# Sheet2.net
KiCad netlist of a schematic drawn in Altium Designer
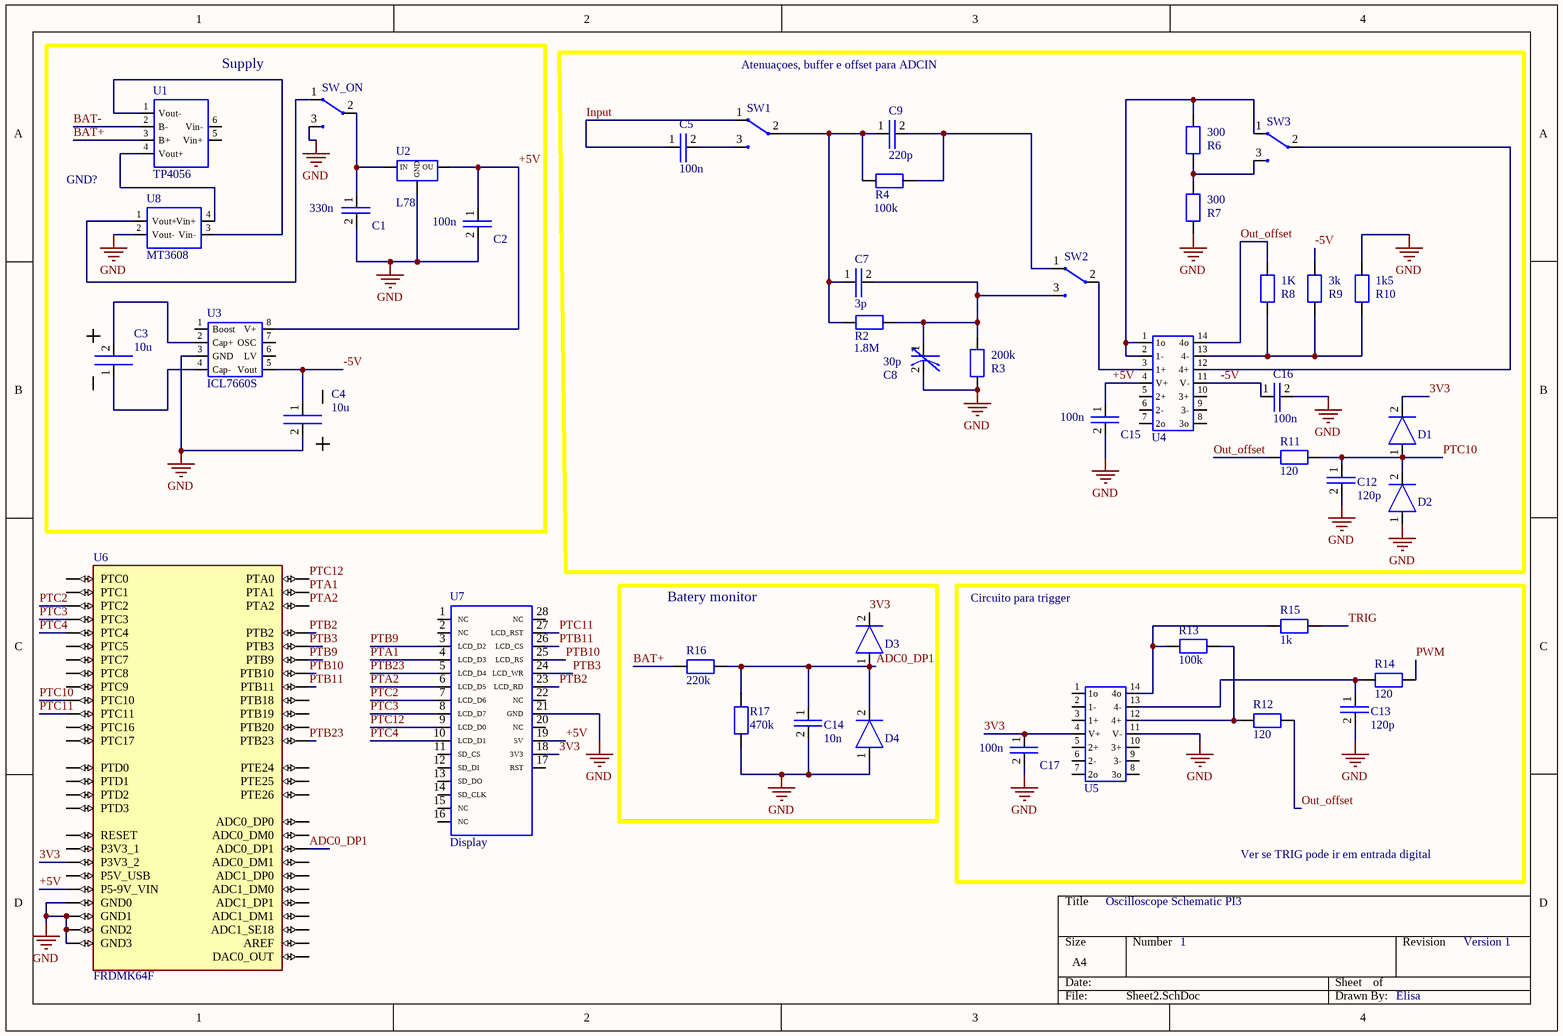
[diagram p0: Sheet2.SchDoc]

(export (version "E")
  (design (tool "Eeschema 10.0.6"))
  (components
    (comp (ref "C1")
      (value "330n")
      (footprint "CAP_CER_THT")
      (libsource (lib "Schlib2") (part "Capacitor_THT"))
    )
    (comp (ref "C2")
      (value "100n")
      (footprint "CAP_CER_THT")
      (libsource (lib "Schlib2") (part "Capacitor_THT"))
    )
    (comp (ref "C3")
      (value "10u")
      (footprint "CAP_THT")
      (description "CAP ALUM 47UF 20% 25V RADIAL TH")
      (libsource (lib "Schlib2") (part "EEU-FC1E470"))
    )
    (comp (ref "C4")
      (value "10u")
      (footprint "CAP_THT")
      (description "CAP ALUM 47UF 20% 25V RADIAL TH")
      (libsource (lib "Schlib2") (part "EEU-FC1E470"))
    )
    (comp (ref "C5")
      (value "100n")
      (footprint "CAP_CER_THT")
      (libsource (lib "Schlib2") (part "Capacitor_THT"))
    )
    (comp (ref "C7")
      (value "3p")
      (footprint "CAP_CER_THT")
      (libsource (lib "Schlib2") (part "Capacitor_THT"))
    )
    (comp (ref "C8")
      (value "30p")
      (footprint "CAP_TRIMM_THT")
      (libsource (lib "Schlib2") (part "CAP_TRIMM_THT"))
    )
    (comp (ref "C9")
      (value "220p")
      (footprint "CAP_CER_THT")
      (libsource (lib "Schlib2") (part "Capacitor_THT"))
    )
    (comp (ref "C12")
      (value "120p")
      (footprint "CAP_CER_THT")
      (libsource (lib "Schlib2") (part "Capacitor_THT"))
    )
    (comp (ref "C13")
      (value "120p")
      (footprint "CAP_CER_THT")
      (libsource (lib "Schlib2") (part "Capacitor_THT"))
    )
    (comp (ref "C14")
      (value "10n")
      (footprint "CAP_CER_THT")
      (libsource (lib "Schlib2") (part "Capacitor_THT"))
    )
    (comp (ref "C15")
      (value "100n")
      (footprint "CAP_CER_THT")
      (libsource (lib "Schlib2") (part "Capacitor_THT"))
    )
    (comp (ref "C16")
      (value "100n")
      (footprint "CAP_CER_THT")
      (libsource (lib "Schlib2") (part "Capacitor_THT"))
    )
    (comp (ref "C17")
      (value "100n")
      (footprint "CAP_CER_THT")
      (libsource (lib "Schlib2") (part "Capacitor_THT"))
    )
    (comp (ref "D1")
      (value "diode_1N4148")
      (footprint "SOD323F_DIODE")
      (libsource (lib "Schlib2") (part "diode_1N4148"))
    )
    (comp (ref "D2")
      (value "diode_1N4148")
      (footprint "SOD323F_DIODE")
      (libsource (lib "Schlib2") (part "diode_1N4148"))
    )
    (comp (ref "D3")
      (value "diode_1N4148")
      (footprint "SOD323F_DIODE")
      (libsource (lib "Schlib2") (part "diode_1N4148"))
    )
    (comp (ref "D4")
      (value "diode_1N4148")
      (footprint "SOD323F_DIODE")
      (libsource (lib "Schlib2") (part "diode_1N4148"))
    )
    (comp (ref "R2") (value "1.8M") (footprint "RES_THT") (libsource (lib "Schlib2") (part "RES_THT")))
    (comp (ref "R3") (value "200k") (footprint "RES_THT") (libsource (lib "Schlib2") (part "RES_THT")))
    (comp (ref "R4") (value "100k") (footprint "RES_THT") (libsource (lib "Schlib2") (part "RES_THT")))
    (comp (ref "R6") (value "300") (footprint "RES_THT") (libsource (lib "Schlib2") (part "RES_THT")))
    (comp (ref "R7") (value "300") (footprint "RES_THT") (libsource (lib "Schlib2") (part "RES_THT")))
    (comp (ref "R8") (value "1K") (footprint "RES_THT") (libsource (lib "Schlib2") (part "RES_THT")))
    (comp (ref "R9") (value "3k") (footprint "RES_THT") (libsource (lib "Schlib2") (part "RES_THT")))
    (comp (ref "R10") (value "1k5") (footprint "RES_THT") (libsource (lib "Schlib2") (part "RES_THT")))
    (comp (ref "R11") (value "120") (footprint "RES_THT") (libsource (lib "Schlib2") (part "RES_THT")))
    (comp (ref "R12") (value "120") (footprint "RES_THT") (libsource (lib "Schlib2") (part "RES_THT")))
    (comp (ref "R13") (value "100k") (footprint "RES_THT") (libsource (lib "Schlib2") (part "RES_THT")))
    (comp (ref "R14") (value "120") (footprint "RES_THT") (libsource (lib "Schlib2") (part "RES_THT")))
    (comp (ref "R15") (value "1k") (footprint "RES_THT") (libsource (lib "Schlib2") (part "RES_THT")))
    (comp (ref "R16") (value "220k") (footprint "RES_THT") (libsource (lib "Schlib2") (part "RES_THT")))
    (comp (ref "R17") (value "470k") (footprint "RES_THT") (libsource (lib "Schlib2") (part "RES_THT")))
    (comp (ref "SW1") (value "SW") (footprint "SW") (libsource (lib "Schlib2") (part "SW")))
    (comp (ref "SW2") (value "SW") (footprint "SW") (libsource (lib "Schlib2") (part "SW")))
    (comp (ref "SW3") (value "SW") (footprint "SW") (libsource (lib "Schlib2") (part "SW")))
    (comp (ref "SW_ON") (value "SW") (footprint "SW") (libsource (lib "Schlib2") (part "SW")))
    (comp (ref "U1") (value "TP4056") (footprint "TP0456") (libsource (lib "Schlib2") (part "TP4056")))
    (comp (ref "U2")
      (value "L78")
      (footprint "TO-220-3")
      (description "IC REG LINEAR 5V 1.5A")
      (libsource (lib "Schlib2") (part "L7805CDT-TR"))
    )
    (comp (ref "U3") (value "ICL7660S") (footprint "8 -PDIP") (libsource (lib "Schlib2") (part "ICL7660S")))
    (comp (ref "U4") (value "TL084CN") (footprint "14-PDIP") (libsource (lib "Schlib2") (part "TL084CN")))
    (comp (ref "U5") (value "TL084CN") (footprint "14-PDIP") (libsource (lib "Schlib2") (part "TL084CN")))
    (comp (ref "U6") (value "FRDMK64F") (footprint "FRDMK64F") (libsource (lib "Schlib2") (part "FRDMK64F")))
    (comp (ref "U7") (value "Display") (footprint "Display") (libsource (lib "Schlib2") (part "Display")))
    (comp (ref "U8") (value "MT3608") (footprint "MT3608") (libsource (lib "Schlib2") (part "MT3608")))
  )
  (nets
    (net (code "1") (name "/+5V") (class "Default")
      (node (ref "C15") (pin "1") (pinfunction "1_1") (pintype "passive"))
      (node (ref "C2") (pin "1") (pinfunction "1_1") (pintype "passive"))
      (node (ref "U2") (pin "3") (pinfunction "OU_3") (pintype "passive"))
      (node (ref "U3") (pin "8") (pinfunction "V+_8") (pintype "passive"))
      (node (ref "U4") (pin "4") (pinfunction "V+_4") (pintype "passive"))
      (node (ref "U6") (pin "J3-16") (pinfunction "P5-9V_VIN_J3-16") (pintype "bidirectional"))
      (node (ref "U7") (pin "19") (pinfunction "5V_19") (pintype "passive"))
    )
    (net (code "2") (name "/-5V") (class "Default")
      (node (ref "C16") (pin "1") (pinfunction "1_1") (pintype "passive"))
      (node (ref "C4") (pin "1") (pinfunction "1_1") (pintype "passive"))
      (node (ref "R9") (pin "2") (pinfunction "2_2") (pintype "passive"))
      (node (ref "U3") (pin "5") (pinfunction "Vout_5") (pintype "passive"))
      (node (ref "U4") (pin "11") (pinfunction "V-_11") (pintype "passive"))
    )
    (net (code "3") (name "/3V3") (class "Default")
      (node (ref "C17") (pin "1") (pinfunction "1_1") (pintype "passive"))
      (node (ref "D1") (pin "2") (pintype "passive"))
      (node (ref "D3") (pin "2") (pintype "passive"))
      (node (ref "U5") (pin "4") (pinfunction "V+_4") (pintype "passive"))
      (node (ref "U6") (pin "J3-8") (pinfunction "P3V3_2_J3-8") (pintype "bidirectional"))
      (node (ref "U7") (pin "18") (pinfunction "3V3_18") (pintype "passive"))
    )
    (net (code "4") (name "/ADC0_DP1") (class "Default")
      (node (ref "C14") (pin "1") (pinfunction "1_1") (pintype "passive"))
      (node (ref "D3") (pin "1") (pintype "passive"))
      (node (ref "D4") (pin "2") (pintype "passive"))
      (node (ref "R16") (pin "1") (pinfunction "1_1") (pintype "passive"))
      (node (ref "R17") (pin "1") (pinfunction "1_1") (pintype "passive"))
      (node (ref "U6") (pin "J4-1") (pinfunction "ADC0_DP1_J4-1") (pintype "bidirectional"))
    )
    (net (code "5") (name "/BAT+") (class "Default")
      (node (ref "R16") (pin "2") (pinfunction "2_2") (pintype "passive"))
      (node (ref "U1") (pin "3") (pinfunction "B+_3") (pintype "passive"))
    )
    (net (code "6") (name "/BAT-") (class "Default")
      (node (ref "U1") (pin "2") (pinfunction "B-_2") (pintype "passive"))
    )
    (net (code "7") (name "/Input") (class "Default")
      (node (ref "C5") (pin "1") (pinfunction "1_1") (pintype "passive"))
      (node (ref "SW1") (pin "1") (pinfunction "1_1") (pintype "passive"))
    )
    (net (code "8") (name "/Out_offset") (class "Default")
      (node (ref "R11") (pin "2") (pinfunction "2_2") (pintype "passive"))
      (node (ref "R12") (pin "1") (pinfunction "1_1") (pintype "passive"))
      (node (ref "R8") (pin "2") (pinfunction "2_2") (pintype "passive"))
      (node (ref "U4") (pin "14") (pinfunction "4o_14") (pintype "passive"))
    )
    (net (code "9") (name "/PTA1") (class "Default")
      (node (ref "U6") (pin "J1-8") (pinfunction "PTA1_J1-8") (pintype "bidirectional"))
      (node (ref "U7") (pin "4") (pinfunction "LCD_D3_4") (pintype "passive"))
    )
    (net (code "10") (name "/PTA2") (class "Default")
      (node (ref "U6") (pin "J1-12") (pinfunction "PTA2_J1-12") (pintype "bidirectional"))
      (node (ref "U7") (pin "6") (pinfunction "LCD_D5_6") (pintype "passive"))
    )
    (net (code "11") (name "/PTB2") (class "Default")
      (node (ref "U6") (pin "J4-2") (pinfunction "PTB2_J4-2") (pintype "bidirectional"))
      (node (ref "U7") (pin "23") (pinfunction "LCD_RD_23") (pintype "passive"))
    )
    (net (code "12") (name "/PTB3") (class "Default")
      (node (ref "U6") (pin "J4-4") (pinfunction "PTB3_J4-4") (pintype "bidirectional"))
      (node (ref "U7") (pin "24") (pinfunction "LCD_WR_24") (pintype "passive"))
    )
    (net (code "13") (name "/PTB9") (class "Default")
      (node (ref "U6") (pin "J1-6") (pinfunction "PTB9_J1-6") (pintype "bidirectional"))
      (node (ref "U7") (pin "3") (pinfunction "LCD_D2_3") (pintype "passive"))
    )
    (net (code "14") (name "/PTB10") (class "Default")
      (node (ref "U6") (pin "J4-6") (pinfunction "PTB10_J4-6") (pintype "bidirectional"))
      (node (ref "U7") (pin "25") (pinfunction "LCD_RS_25") (pintype "passive"))
    )
    (net (code "15") (name "/PTB11") (class "Default")
      (node (ref "U6") (pin "J4-8") (pinfunction "PTB11_J4-8") (pintype "bidirectional"))
      (node (ref "U7") (pin "26") (pinfunction "LCD_CS_26") (pintype "passive"))
    )
    (net (code "16") (name "/PTB23") (class "Default")
      (node (ref "U6") (pin "J1-10") (pinfunction "PTB23_J1-10") (pintype "bidirectional"))
      (node (ref "U7") (pin "5") (pinfunction "LCD_D4_5") (pintype "passive"))
    )
    (net (code "17") (name "/PTC2") (class "Default")
      (node (ref "U6") (pin "J1-14") (pinfunction "PTC2_J1-14") (pintype "bidirectional"))
      (node (ref "U7") (pin "7") (pinfunction "LCD_D6_7") (pintype "passive"))
    )
    (net (code "18") (name "/PTC3") (class "Default")
      (node (ref "U6") (pin "J1-16") (pinfunction "PTC3_J1-16") (pintype "bidirectional"))
      (node (ref "U7") (pin "8") (pinfunction "LCD_D7_8") (pintype "passive"))
    )
    (net (code "19") (name "/PTC4") (class "Default")
      (node (ref "U6") (pin "J2-4") (pinfunction "PTC4_J2-4") (pintype "bidirectional"))
      (node (ref "U7") (pin "10") (pinfunction "LCD_D1_10") (pintype "passive"))
    )
    (net (code "20") (name "/PTC10") (class "Default")
      (node (ref "C12") (pin "1") (pinfunction "1_1") (pintype "passive"))
      (node (ref "D1") (pin "1") (pintype "passive"))
      (node (ref "D2") (pin "2") (pintype "passive"))
      (node (ref "R11") (pin "1") (pinfunction "1_1") (pintype "passive"))
      (node (ref "U6") (pin "J4-12") (pinfunction "PTC10_J4-12") (pintype "bidirectional"))
    )
    (net (code "21") (name "/PTC11") (class "Default")
      (node (ref "U6") (pin "J4-10") (pinfunction "PTC11_J4-10") (pintype "bidirectional"))
      (node (ref "U7") (pin "27") (pinfunction "LCD_RST_27") (pintype "passive"))
    )
    (net (code "22") (name "/PTC12") (class "Default")
      (node (ref "U6") (pin "J2-2") (pinfunction "PTA0_J2-2") (pintype "bidirectional"))
      (node (ref "U7") (pin "9") (pinfunction "LCD_D0_9") (pintype "passive"))
    )
    (net (code "23") (name "/PWM") (class "Default")
      (node (ref "R14") (pin "1") (pinfunction "1_1") (pintype "passive"))
    )
    (net (code "24") (name "/TRIG") (class "Default")
      (node (ref "R15") (pin "2") (pinfunction "2_2") (pintype "passive"))
    )
    (net (code "25") (name "GND") (class "Default")
      (node (ref "C1") (pin "2") (pinfunction "0_2") (pintype "passive"))
      (node (ref "C12") (pin "2") (pinfunction "0_2") (pintype "passive"))
      (node (ref "C13") (pin "2") (pinfunction "0_2") (pintype "passive"))
      (node (ref "C14") (pin "2") (pinfunction "0_2") (pintype "passive"))
      (node (ref "C15") (pin "2") (pinfunction "0_2") (pintype "passive"))
      (node (ref "C16") (pin "2") (pinfunction "0_2") (pintype "passive"))
      (node (ref "C17") (pin "2") (pinfunction "0_2") (pintype "passive"))
      (node (ref "C2") (pin "2") (pinfunction "0_2") (pintype "passive"))
      (node (ref "C4") (pin "2") (pinfunction "0_2") (pintype "passive"))
      (node (ref "C8") (pin "2") (pinfunction "0_2") (pintype "passive"))
      (node (ref "D2") (pin "1") (pintype "passive"))
      (node (ref "D4") (pin "1") (pintype "passive"))
      (node (ref "R10") (pin "2") (pinfunction "2_2") (pintype "passive"))
      (node (ref "R17") (pin "2") (pinfunction "2_2") (pintype "passive"))
      (node (ref "R3") (pin "1") (pinfunction "1_1") (pintype "passive"))
      (node (ref "R7") (pin "1") (pinfunction "1_1") (pintype "passive"))
      (node (ref "SW_ON") (pin "3") (pinfunction "3_3") (pintype "passive"))
      (node (ref "U2") (pin "2") (pinfunction "GND_2") (pintype "passive"))
      (node (ref "U3") (pin "3") (pinfunction "GND_3") (pintype "passive"))
      (node (ref "U5") (pin "11") (pinfunction "V-_11") (pintype "passive"))
      (node (ref "U6") (pin "J2-14") (pinfunction "GND1_J2-14") (pintype "bidirectional"))
      (node (ref "U6") (pin "J2-3") (pinfunction "GND0_J2-3") (pintype "bidirectional"))
      (node (ref "U6") (pin "J3-12") (pinfunction "GND2_J3-12") (pintype "bidirectional"))
      (node (ref "U6") (pin "J3-14") (pinfunction "GND3_J3-14") (pintype "bidirectional"))
      (node (ref "U7") (pin "21") (pinfunction "GND_21") (pintype "passive"))
      (node (ref "U8") (pin "2") (pinfunction "Vout-_2") (pintype "passive"))
    )
    (net (code "26") (name "Net-(C3-0)") (class "Default")
      (node (ref "C3") (pin "2") (pinfunction "0_2") (pintype "passive"))
      (node (ref "U3") (pin "2") (pinfunction "Cap+_2") (pintype "passive"))
    )
    (net (code "27") (name "Net-(C5-0)") (class "Default")
      (node (ref "C5") (pin "2") (pinfunction "0_2") (pintype "passive"))
      (node (ref "SW1") (pin "3") (pinfunction "3_3") (pintype "passive"))
    )
    (net (code "28") (name "Net-(C7-0)") (class "Default")
      (node (ref "C7") (pin "2") (pinfunction "0_2") (pintype "passive"))
      (node (ref "C8") (pin "1") (pinfunction "1_1") (pintype "passive"))
      (node (ref "R2") (pin "2") (pinfunction "2_2") (pintype "passive"))
      (node (ref "R3") (pin "2") (pinfunction "2_2") (pintype "passive"))
      (node (ref "SW2") (pin "3") (pinfunction "3_3") (pintype "passive"))
    )
    (net (code "29") (name "Net-(C7-Pad1)") (class "Default")
      (node (ref "C7") (pin "1") (pinfunction "1_1") (pintype "passive"))
      (node (ref "C9") (pin "1") (pinfunction "1_1") (pintype "passive"))
      (node (ref "R2") (pin "1") (pinfunction "1_1") (pintype "passive"))
      (node (ref "R4") (pin "1") (pinfunction "1_1") (pintype "passive"))
      (node (ref "SW1") (pin "2") (pinfunction "2_2") (pintype "passive"))
    )
    (net (code "30") (name "Net-(C9-0)") (class "Default")
      (node (ref "C9") (pin "2") (pinfunction "0_2") (pintype "passive"))
      (node (ref "R4") (pin "2") (pinfunction "2_2") (pintype "passive"))
      (node (ref "SW2") (pin "1") (pinfunction "1_1") (pintype "passive"))
    )
    (net (code "31") (name "Net-(R6-Pad1)") (class "Default")
      (node (ref "R6") (pin "1") (pinfunction "1_1") (pintype "passive"))
      (node (ref "R7") (pin "2") (pinfunction "2_2") (pintype "passive"))
      (node (ref "SW3") (pin "3") (pinfunction "3_3") (pintype "passive"))
    )
    (net (code "32") (name "Net-(U1-Vout+)") (class "Default")
      (node (ref "U1") (pin "4") (pinfunction "Vout+_4") (pintype "passive"))
      (node (ref "U8") (pin "4") (pinfunction "Vin+_4") (pintype "passive"))
    )
    (net (code "33") (name "Net-(U1-Vout-)") (class "Default")
      (node (ref "U1") (pin "1") (pinfunction "Vout-_1") (pintype "passive"))
      (node (ref "U8") (pin "3") (pinfunction "Vin-_3") (pintype "passive"))
    )
    (net (code "34") (name "Net-(U2-IN)") (class "Default")
      (node (ref "C1") (pin "1") (pinfunction "1_1") (pintype "passive"))
      (node (ref "SW_ON") (pin "2") (pinfunction "2_2") (pintype "passive"))
      (node (ref "U2") (pin "1") (pinfunction "IN_1") (pintype "passive"))
    )
    (net (code "35") (name "Net-(U3-Cap-)") (class "Default")
      (node (ref "C3") (pin "1") (pinfunction "1_1") (pintype "passive"))
      (node (ref "U3") (pin "4") (pinfunction "Cap-_4") (pintype "passive"))
    )
    (net (code "36") (name "Net-(U4-1+)") (class "Default")
      (node (ref "SW2") (pin "2") (pinfunction "2_2") (pintype "passive"))
      (node (ref "U4") (pin "3") (pinfunction "1+_3") (pintype "passive"))
    )
    (net (code "37") (name "Net-(U4-1-)") (class "Default")
      (node (ref "R6") (pin "2") (pinfunction "2_2") (pintype "passive"))
      (node (ref "SW3") (pin "1") (pinfunction "1_1") (pintype "passive"))
      (node (ref "U4") (pin "1") (pinfunction "1o_1") (pintype "passive"))
      (node (ref "U4") (pin "2") (pinfunction "1-_2") (pintype "passive"))
    )
    (net (code "38") (name "Net-(U4-4+)") (class "Default")
      (node (ref "SW3") (pin "2") (pinfunction "2_2") (pintype "passive"))
      (node (ref "U4") (pin "12") (pinfunction "4+_12") (pintype "passive"))
    )
    (net (code "39") (name "Net-(U4-4-)") (class "Default")
      (node (ref "R10") (pin "1") (pinfunction "1_1") (pintype "passive"))
      (node (ref "R8") (pin "1") (pinfunction "1_1") (pintype "passive"))
      (node (ref "R9") (pin "1") (pinfunction "1_1") (pintype "passive"))
      (node (ref "U4") (pin "13") (pinfunction "4-_13") (pintype "passive"))
    )
    (net (code "40") (name "Net-(U5-4+)") (class "Default")
      (node (ref "R12") (pin "2") (pinfunction "2_2") (pintype "passive"))
      (node (ref "R13") (pin "1") (pinfunction "1_1") (pintype "passive"))
      (node (ref "U5") (pin "12") (pinfunction "4+_12") (pintype "passive"))
    )
    (net (code "41") (name "Net-(U5-4-)") (class "Default")
      (node (ref "C13") (pin "1") (pinfunction "1_1") (pintype "passive"))
      (node (ref "R14") (pin "2") (pinfunction "2_2") (pintype "passive"))
      (node (ref "U5") (pin "13") (pinfunction "4-_13") (pintype "passive"))
    )
    (net (code "42") (name "Net-(U5-4o)") (class "Default")
      (node (ref "R13") (pin "2") (pinfunction "2_2") (pintype "passive"))
      (node (ref "R15") (pin "1") (pinfunction "1_1") (pintype "passive"))
      (node (ref "U5") (pin "14") (pinfunction "4o_14") (pintype "passive"))
    )
    (net (code "43") (name "Net-(U8-Vout+)") (class "Default")
      (node (ref "SW_ON") (pin "1") (pinfunction "1_1") (pintype "passive"))
      (node (ref "U8") (pin "1") (pinfunction "Vout+_1") (pintype "passive"))
    )
    (net (code "44") (name "unconnected-(U1-Vin+-Pad5)") (class "Default")
      (node (ref "U1") (pin "5") (pinfunction "Vin+_5") (pintype "passive"))
    )
    (net (code "45") (name "unconnected-(U1-Vin--Pad6)") (class "Default")
      (node (ref "U1") (pin "6") (pinfunction "Vin-_6") (pintype "passive"))
    )
    (net (code "46") (name "unconnected-(U3-Boost-Pad1)") (class "Default")
      (node (ref "U3") (pin "1") (pinfunction "Boost_1") (pintype "passive"))
    )
    (net (code "47") (name "unconnected-(U3-LV-Pad6)") (class "Default")
      (node (ref "U3") (pin "6") (pinfunction "LV_6") (pintype "passive"))
    )
    (net (code "48") (name "unconnected-(U3-OSC-Pad7)") (class "Default")
      (node (ref "U3") (pin "7") (pinfunction "OSC_7") (pintype "passive"))
    )
    (net (code "49") (name "unconnected-(U4-2+-Pad5)") (class "Default")
      (node (ref "U4") (pin "5") (pinfunction "2+_5") (pintype "passive"))
    )
    (net (code "50") (name "unconnected-(U4-2--Pad6)") (class "Default")
      (node (ref "U4") (pin "6") (pinfunction "2-_6") (pintype "passive"))
    )
    (net (code "51") (name "unconnected-(U4-2o-Pad7)") (class "Default")
      (node (ref "U4") (pin "7") (pinfunction "2o_7") (pintype "passive"))
    )
    (net (code "52") (name "unconnected-(U4-3+-Pad10)") (class "Default")
      (node (ref "U4") (pin "10") (pinfunction "3+_10") (pintype "passive"))
    )
    (net (code "53") (name "unconnected-(U4-3--Pad9)") (class "Default")
      (node (ref "U4") (pin "9") (pinfunction "3-_9") (pintype "passive"))
    )
    (net (code "54") (name "unconnected-(U4-3o-Pad8)") (class "Default")
      (node (ref "U4") (pin "8") (pinfunction "3o_8") (pintype "passive"))
    )
    (net (code "55") (name "unconnected-(U5-1+-Pad3)") (class "Default")
      (node (ref "U5") (pin "3") (pinfunction "1+_3") (pintype "passive"))
    )
    (net (code "56") (name "unconnected-(U5-1--Pad2)") (class "Default")
      (node (ref "U5") (pin "2") (pinfunction "1-_2") (pintype "passive"))
    )
    (net (code "57") (name "unconnected-(U5-1o-Pad1)") (class "Default")
      (node (ref "U5") (pin "1") (pinfunction "1o_1") (pintype "passive"))
    )
    (net (code "58") (name "unconnected-(U5-2+-Pad5)") (class "Default")
      (node (ref "U5") (pin "5") (pinfunction "2+_5") (pintype "passive"))
    )
    (net (code "59") (name "unconnected-(U5-2--Pad6)") (class "Default")
      (node (ref "U5") (pin "6") (pinfunction "2-_6") (pintype "passive"))
    )
    (net (code "60") (name "unconnected-(U5-2o-Pad7)") (class "Default")
      (node (ref "U5") (pin "7") (pinfunction "2o_7") (pintype "passive"))
    )
    (net (code "61") (name "unconnected-(U5-3+-Pad10)") (class "Default")
      (node (ref "U5") (pin "10") (pinfunction "3+_10") (pintype "passive"))
    )
    (net (code "62") (name "unconnected-(U5-3--Pad9)") (class "Default")
      (node (ref "U5") (pin "9") (pinfunction "3-_9") (pintype "passive"))
    )
    (net (code "63") (name "unconnected-(U5-3o-Pad8)") (class "Default")
      (node (ref "U5") (pin "8") (pinfunction "3o_8") (pintype "passive"))
    )
    (net (code "64") (name "unconnected-(U6-ADC0_DM0-PadJ2-7)") (class "Default")
      (node (ref "U6") (pin "J2-7") (pinfunction "ADC0_DM0_J2-7") (pintype "bidirectional"))
    )
    (net (code "65") (name "unconnected-(U6-ADC0_DM1-PadJ4-3)") (class "Default")
      (node (ref "U6") (pin "J4-3") (pinfunction "ADC0_DM1_J4-3") (pintype "bidirectional"))
    )
    (net (code "66") (name "unconnected-(U6-ADC0_DP0-PadJ2-5)") (class "Default")
      (node (ref "U6") (pin "J2-5") (pinfunction "ADC0_DP0_J2-5") (pintype "bidirectional"))
    )
    (net (code "67") (name "unconnected-(U6-ADC1_DM0-PadJ2-13)") (class "Default")
      (node (ref "U6") (pin "J2-13") (pinfunction "ADC1_DM0_J2-13") (pintype "bidirectional"))
    )
    (net (code "68") (name "unconnected-(U6-ADC1_DM1-PadJ4-7)") (class "Default")
      (node (ref "U6") (pin "J4-7") (pinfunction "ADC1_DM1_J4-7") (pintype "bidirectional"))
    )
    (net (code "69") (name "unconnected-(U6-ADC1_DP0-PadJ2-11)") (class "Default")
      (node (ref "U6") (pin "J2-11") (pinfunction "ADC1_DP0_J2-11") (pintype "bidirectional"))
    )
    (net (code "70") (name "unconnected-(U6-ADC1_DP1-PadJ4-5)") (class "Default")
      (node (ref "U6") (pin "J4-5") (pinfunction "ADC1_DP1_J4-5") (pintype "bidirectional"))
    )
    (net (code "71") (name "unconnected-(U6-ADC1_SE18-PadJ2-17)") (class "Default")
      (node (ref "U6") (pin "J2-17") (pinfunction "ADC1_SE18_J2-17") (pintype "bidirectional"))
    )
    (net (code "72") (name "unconnected-(U6-AREF-PadJ2-16)") (class "Default")
      (node (ref "U6") (pin "J2-16") (pinfunction "AREF_J2-16") (pintype "bidirectional"))
    )
    (net (code "73") (name "unconnected-(U6-DAC0_OUT-PadJ4-11)") (class "Default")
      (node (ref "U6") (pin "J4-11") (pinfunction "DAC0_OUT_J4-11") (pintype "bidirectional"))
    )
    (net (code "74") (name "unconnected-(U6-P3V3_1-PadJ3-4)") (class "Default")
      (node (ref "U6") (pin "J3-4") (pinfunction "P3V3_1_J3-4") (pintype "bidirectional"))
    )
    (net (code "75") (name "unconnected-(U6-P5V_USB-PadJ3-10)") (class "Default")
      (node (ref "U6") (pin "J3-10") (pinfunction "P5V_USB_J3-10") (pintype "bidirectional"))
    )
    (net (code "76") (name "unconnected-(U6-PTB18-PadJ1-1)") (class "Default")
      (node (ref "U6") (pin "J1-1") (pinfunction "PTB18_J1-1") (pintype "bidirectional"))
    )
    (net (code "77") (name "unconnected-(U6-PTB19-PadJ1-3)") (class "Default")
      (node (ref "U6") (pin "J1-3") (pinfunction "PTB19_J1-3") (pintype "bidirectional"))
    )
    (net (code "78") (name "unconnected-(U6-PTB20-PadJ4-9)") (class "Default")
      (node (ref "U6") (pin "J4-9") (pinfunction "PTB20_J4-9") (pintype "bidirectional"))
    )
    (net (code "79") (name "unconnected-(U6-PTC0-PadJ1-11)") (class "Default")
      (node (ref "U6") (pin "J1-11") (pinfunction "PTC0_J1-11") (pintype "bidirectional"))
    )
    (net (code "80") (name "unconnected-(U6-PTC1-PadJ1-5)") (class "Default")
      (node (ref "U6") (pin "J1-5") (pinfunction "PTC1_J1-5") (pintype "bidirectional"))
    )
    (net (code "81") (name "unconnected-(U6-PTC5-PadJ1-15)") (class "Default")
      (node (ref "U6") (pin "J1-15") (pinfunction "PTC5_J1-15") (pintype "bidirectional"))
    )
    (net (code "82") (name "unconnected-(U6-PTC7-PadJ1-13)") (class "Default")
      (node (ref "U6") (pin "J1-13") (pinfunction "PTC7_J1-13") (pintype "bidirectional"))
    )
    (net (code "83") (name "unconnected-(U6-PTC8-PadJ1-7)") (class "Default")
      (node (ref "U6") (pin "J1-7") (pinfunction "PTC8_J1-7") (pintype "bidirectional"))
    )
    (net (code "84") (name "unconnected-(U6-PTC9-PadJ1-9)") (class "Default")
      (node (ref "U6") (pin "J1-9") (pinfunction "PTC9_J1-9") (pintype "bidirectional"))
    )
    (net (code "85") (name "unconnected-(U6-PTC16-PadJ1-2)") (class "Default")
      (node (ref "U6") (pin "J1-2") (pinfunction "PTC16_J1-2") (pintype "bidirectional"))
    )
    (net (code "86") (name "unconnected-(U6-PTC17-PadJ1-4)") (class "Default")
      (node (ref "U6") (pin "J1-4") (pinfunction "PTC17_J1-4") (pintype "bidirectional"))
    )
    (net (code "87") (name "unconnected-(U6-PTD0-PadJ2-6)") (class "Default")
      (node (ref "U6") (pin "J2-6") (pinfunction "PTD0_J2-6") (pintype "bidirectional"))
    )
    (net (code "88") (name "unconnected-(U6-PTD1-PadJ2-12)") (class "Default")
      (node (ref "U6") (pin "J2-12") (pinfunction "PTD1_J2-12") (pintype "bidirectional"))
    )
    (net (code "89") (name "unconnected-(U6-PTD2-PadJ2-8)") (class "Default")
      (node (ref "U6") (pin "J2-8") (pinfunction "PTD2_J2-8") (pintype "bidirectional"))
    )
    (net (code "90") (name "unconnected-(U6-PTD3-PadJ2-10)") (class "Default")
      (node (ref "U6") (pin "J2-10") (pinfunction "PTD3_J2-10") (pintype "bidirectional"))
    )
    (net (code "91") (name "unconnected-(U6-PTE24-PadJ2-20)") (class "Default")
      (node (ref "U6") (pin "J2-20") (pinfunction "PTE24_J2-20") (pintype "bidirectional"))
    )
    (net (code "92") (name "unconnected-(U6-PTE25-PadJ2-18)") (class "Default")
      (node (ref "U6") (pin "J2-18") (pinfunction "PTE25_J2-18") (pintype "bidirectional"))
    )
    (net (code "93") (name "unconnected-(U6-PTE26-PadJ2-1)") (class "Default")
      (node (ref "U6") (pin "J2-1") (pinfunction "PTE26_J2-1") (pintype "bidirectional"))
    )
    (net (code "94") (name "unconnected-(U6-RESET-PadJ3-6)") (class "Default")
      (node (ref "U6") (pin "J3-6") (pinfunction "RESET_J3-6") (pintype "bidirectional"))
    )
    (net (code "95") (name "unconnected-(U7-NC-Pad1)") (class "Default")
      (node (ref "U7") (pin "1") (pinfunction "NC_1") (pintype "passive"))
    )
    (net (code "96") (name "unconnected-(U7-NC-Pad2)") (class "Default")
      (node (ref "U7") (pin "2") (pinfunction "NC_2") (pintype "passive"))
    )
    (net (code "97") (name "unconnected-(U7-NC-Pad15)") (class "Default")
      (node (ref "U7") (pin "15") (pinfunction "NC_15") (pintype "passive"))
    )
    (net (code "98") (name "unconnected-(U7-NC-Pad16)") (class "Default")
      (node (ref "U7") (pin "16") (pinfunction "NC_16") (pintype "passive"))
    )
    (net (code "99") (name "unconnected-(U7-NC-Pad20)") (class "Default")
      (node (ref "U7") (pin "20") (pinfunction "NC_20") (pintype "passive"))
    )
    (net (code "100") (name "unconnected-(U7-NC-Pad22)") (class "Default")
      (node (ref "U7") (pin "22") (pinfunction "NC_22") (pintype "passive"))
    )
    (net (code "101") (name "unconnected-(U7-NC-Pad28)") (class "Default")
      (node (ref "U7") (pin "28") (pinfunction "NC_28") (pintype "passive"))
    )
    (net (code "102") (name "unconnected-(U7-RST-Pad17)") (class "Default")
      (node (ref "U7") (pin "17") (pinfunction "RST_17") (pintype "passive"))
    )
    (net (code "103") (name "unconnected-(U7-SD_CLK-Pad14)") (class "Default")
      (node (ref "U7") (pin "14") (pinfunction "SD_CLK_14") (pintype "passive"))
    )
    (net (code "104") (name "unconnected-(U7-SD_CS-Pad11)") (class "Default")
      (node (ref "U7") (pin "11") (pinfunction "SD_CS_11") (pintype "passive"))
    )
    (net (code "105") (name "unconnected-(U7-SD_DI-Pad12)") (class "Default")
      (node (ref "U7") (pin "12") (pinfunction "SD_DI_12") (pintype "passive"))
    )
    (net (code "106") (name "unconnected-(U7-SD_DO-Pad13)") (class "Default")
      (node (ref "U7") (pin "13") (pinfunction "SD_DO_13") (pintype "passive"))
    )
  )
)
